# Sheet1.net
KiCad netlist of a schematic drawn in Altium Designer
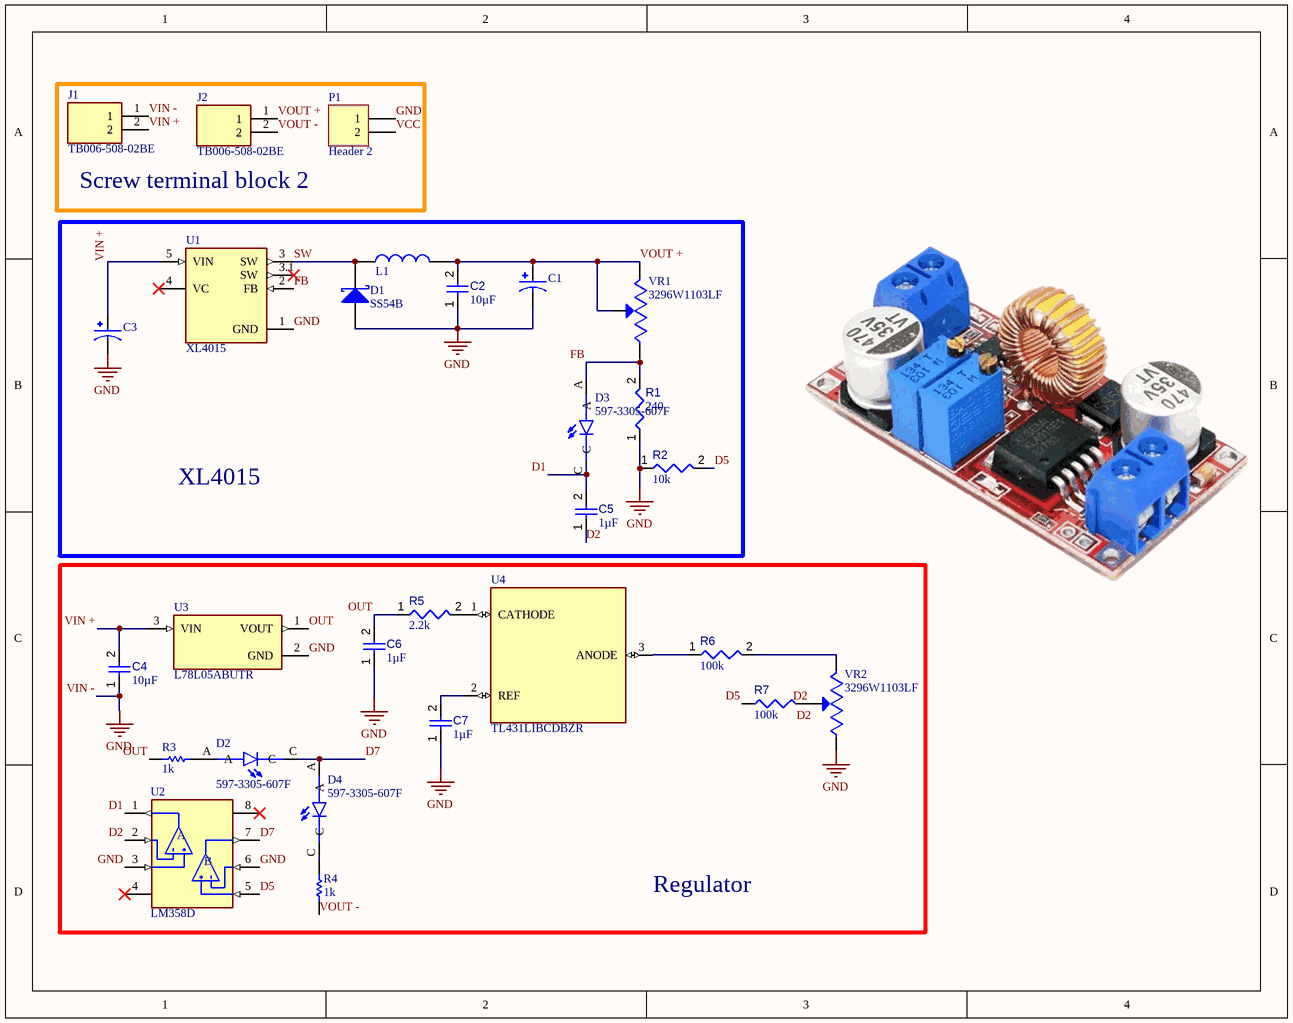
[diagram p0: Sheet1.SchDoc]

(export (version "E")
  (design (tool "Eeschema 10.0.6"))
  (components
    (comp (ref "C1")
      (value "EEEFN1V471UP")
      (footprint "CAP_EEEFN1V471UP")
      (description "CAP ALUM 470UF 20% 35V SMD")
      (fields (field (name "MF") "Panasonic Electronic Components") (field (name "MP") "EEE-FN1V471UP"))
      (libsource (lib "CAP ALUM 470UF") (part "EEEFN1V471UP"))
    )
    (comp (ref "C2")
      (value "10µF")
      (footprint "CAPC0603(1608)100_L")
      (description "Chip Capacitor, 10µF +/-20%, 10V, 0603, Thickness 1 mm")
      (fields (field (name "TOLERANCE") "10%") (field (name "Comment") "Capacitor 10µF +/-20% 10V 0603"))
      (libsource (lib "Med khalil khlifi") (part "CAP-NP-2"))
    )
    (comp (ref "C3")
      (value "EEEFN1V471UP")
      (footprint "CAP_EEEFN1V471UP")
      (description "CAP ALUM 470UF 20% 35V SMD")
      (fields (field (name "MF") "Panasonic Electronic Components") (field (name "MP") "EEE-FN1V471UP"))
      (libsource (lib "CAP ALUM 470UF") (part "EEEFN1V471UP"))
    )
    (comp (ref "C4")
      (value "10µF")
      (footprint "CAPC0603(1608)100_L")
      (description "Chip Capacitor, 10µF +/-20%, 10V, 0603, Thickness 1 mm")
      (fields (field (name "TOLERANCE") "10%") (field (name "Comment") "Capacitor 10µF +/-20% 10V 0603"))
      (libsource (lib "Med khalil khlifi") (part "CAP-NP-2"))
    )
    (comp (ref "C5")
      (value "1µF")
      (footprint "CAPC2013X145X50ML20T25")
      (description "Chip Capacitor, 1 uF, +/-10%, 25 V, 0805 (2012 Metric)")
      (fields (field (name "TOLERANCE") "10%") (field (name "Comment") "Capacitor 1 uF +/- 10% 25 V 0805"))
      (libsource (lib "Med khalil khlifi") (part "CAP-NP-2"))
    )
    (comp (ref "C6")
      (value "1µF")
      (footprint "CAPC2013X145X50ML20T25")
      (description "Chip Capacitor, 1 uF, +/-10%, 25 V, 0805 (2012 Metric)")
      (fields (field (name "TOLERANCE") "10%") (field (name "Comment") "Capacitor 1 uF +/- 10% 25 V 0805"))
      (libsource (lib "Med khalil khlifi") (part "CAP-NP-2"))
    )
    (comp (ref "C7")
      (value "1µF")
      (footprint "CAPC2013X145X50ML20T25")
      (description "Chip Capacitor, 1 uF, +/-10%, 25 V, 0805 (2012 Metric)")
      (fields (field (name "TOLERANCE") "10%") (field (name "Comment") "Capacitor 1 uF +/- 10% 25 V 0805"))
      (libsource (lib "Med khalil khlifi") (part "CAP-NP-2"))
    )
    (comp (ref "D1")
      (value "SS54B")
      (footprint "JCET-SMB-2_M")
      (description "Schottky Barrier Rectifier, 40 V, 5 A, -55 to 150 degC, 2-Pin SMD")
      (fields (field (name "MANUFACTURER") "JCET"))
      (libsource (lib "Med khalil khlifi") (part "DSKY-AK-2"))
    )
    (comp (ref "D2")
      (value "597-3305-607F")
      (footprint "LEDC2012X70N")
      (description "LED Uni-Color Green 4-Pin Chip 0805 T/R")
      (libsource (lib "Led") (part "597-3305-607F"))
    )
    (comp (ref "D3")
      (value "597-3305-607F")
      (footprint "LEDC2012X70N")
      (description "LED Uni-Color Green 4-Pin Chip 0805 T/R")
      (libsource (lib "Led") (part "597-3305-607F"))
    )
    (comp (ref "D4")
      (value "597-3305-607F")
      (footprint "LEDC2012X70N")
      (description "LED Uni-Color Green 4-Pin Chip 0805 T/R")
      (libsource (lib "Led") (part "597-3305-607F"))
    )
    (comp (ref "J1")
      (value "TB006-508-02BE")
      (footprint "CUI_TB006-508-02BE")
      (description "2~24 Poles, Screw Type, Horizontal, 5.08 Pitch, 26~14 (AWG), Terminal Block Connector")
      (fields (field (name "MF") "Same Sky"))
      (libsource (lib "screw terminal block 2") (part "TB006-508-02BE"))
    )
    (comp (ref "J2")
      (value "TB006-508-02BE")
      (footprint "CUI_TB006-508-02BE")
      (description "2~24 Poles, Screw Type, Horizontal, 5.08 Pitch, 26~14 (AWG), Terminal Block Connector")
      (fields (field (name "MF") "Same Sky"))
      (libsource (lib "screw terminal block 2") (part "TB006-508-02BE"))
    )
    (comp (ref "L1")
      (value "15µH")
      (footprint "7447035")
      (description "WE-FI THT Leaded Toroidal Line Choke, 15µH, 4.5A, 0.025Ω")
      (fields
        (field (name "MANUFACTURER PART NUMBER") "7447035")
        (field (name "MANUFACTURER") "Wurth Elektronik")
      )
      (libsource (lib "Toroidal Inductor") (part "7447035"))
    )
    (comp (ref "P1")
      (value "Header 2")
      (footprint "HDR1X2")
      (description "Header, 2-Pin")
      (fields (field (name "PUBLISHER") "Altium Limited"))
      (libsource (lib "Med khalil khlifi") (part "Header 2H"))
    )
    (comp (ref "R1")
      (value "240")
      (footprint "RESC0402(1005)_L")
      (description "Chip Resistor, 240 Ohms, +/-5 %, 63 mW, -55 to 155 degC, 0402")
      (fields (field (name "POWER") "63mW") (field (name "TOLERANCE") "5%"))
      (libsource (lib "") (part "RES-2_1"))
    )
    (comp (ref "R2")
      (value "10k")
      (footprint "RESC0402(1005)_L")
      (description "Chip Resistor, 10 kOhms, +/-1 %, 63 mW, -55 to 125 degC, 0402")
      (fields (field (name "POWER") "63mW") (field (name "TOLERANCE") "1%"))
      (libsource (lib "") (part "RES-2_1"))
    )
    (comp (ref "R3")
      (value "1k")
      (footprint "RESC1005X40X25ML05T05")
      (description "Chip Resistor, 1 KOhm, +/- 1%, 0.1 W, -55 to 155 degC, 0402 (1005 Metric)")
      (fields (field (name "POWER") "100mW") (field (name "TOLERANCE") "1%"))
      (libsource (lib "Med khalil khlifi") (part "RES-2"))
    )
    (comp (ref "R4")
      (value "1k")
      (footprint "RESC1005X40X25ML05T05")
      (description "Chip Resistor, 1 KOhm, +/- 1%, 0.1 W, -55 to 155 degC, 0402 (1005 Metric)")
      (fields (field (name "POWER") "100mW") (field (name "TOLERANCE") "1%"))
      (libsource (lib "Med khalil khlifi") (part "RES-2"))
    )
    (comp (ref "R5")
      (value "2.2k")
      (footprint "RESC0402(1005)_L")
      (description "Chip Resistor, 2,2 kOhms, +/-5 %, 63 mW, -55 to 155 degC, 0402")
      (fields (field (name "POWER") "63mW") (field (name "TOLERANCE") "5%"))
      (libsource (lib "") (part "RES-2_1"))
    )
    (comp (ref "R6")
      (value "100k")
      (footprint "RESC1005X40X25ML05T05")
      (description "Chip Resistor, 100 KOhm, +/- 1%, 0.063 W, -55 to 155 degC, 0402 (1005 Metric)")
      (fields (field (name "TOLERANCE") "1%") (field (name "POWER") "63mW"))
      (libsource (lib "") (part "RES-2_1"))
    )
    (comp (ref "R7")
      (value "100k")
      (footprint "RESC1005X40X25ML05T05")
      (description "Chip Resistor, 100 KOhm, +/- 1%, 0.063 W, -55 to 155 degC, 0402 (1005 Metric)")
      (fields (field (name "TOLERANCE") "1%") (field (name "POWER") "63mW"))
      (libsource (lib "") (part "RES-2_2"))
    )
    (comp (ref "U1")
      (value "XL4015")
      (footprint "CONV_XL4015")
      (description "5A 180KHz 36V Buck DC to DC Converter")
      (fields (field (name "MF") "XLSEMI"))
      (libsource (lib "XL4015") (part "XL4015"))
    )
    (comp (ref "U2")
      (value "LM358D")
      (footprint "SOIC127P599X175-8N")
      (description "Op Amp Dual Low Power Amplifier Â±15V/30V 8-Pin SO N Tube")
      (fields (field (name "MF") "STMicroelectronics"))
      (libsource (lib "LM358D") (part "LM358D"))
    )
    (comp (ref "U3")
      (value "L78L05ABUTR")
      (footprint "VREG_L78L05ABUTR")
      (description "Linear Voltage Regulator IC Positive Fixed 1 Output 100mA SOT-89-3")
      (fields (field (name "MF") "STMicroelectronics"))
      (libsource (lib "L78L05ABUTR") (part "L78L05ABUTR"))
    )
    (comp (ref "U4")
      (value "TL431LIBCDBZR")
      (footprint "SOT23")
      (description "Adjustable precision shunt regulator with optimized reference current (pin layout: KRA)")
      (fields (field (name "MF") "Texas Instruments"))
      (libsource (lib "TL431LIBCDBZR") (part "TL431LIBCDBZR"))
    )
    (comp (ref "VR1")
      (value "3296W1103LF")
      (footprint "TRIM_3296W1103LF")
      (description "Trimmer, Potentiometer 10kohm 25turn Thd")
      (fields (field (name "MF") "Bourns"))
      (libsource (lib "Potentiometer 1") (part "3296W1103LF"))
    )
    (comp (ref "VR2")
      (value "3296W1103LF")
      (footprint "TRIM_3296W1103LF")
      (description "Trimmer, Potentiometer 10kohm 25turn Thd")
      (fields (field (name "MF") "Bourns"))
      (libsource (lib "Potentiometer 1") (part "3296W1103LF"))
    )
  )
  (nets
    (net (code "1") (name "/D1") (class "Default")
      (node (ref "C5") (pin "2") (pinfunction "2_2") (pintype "passive"))
      (node (ref "D3") (pin "C") (pinfunction "C_C") (pintype "passive"))
      (node (ref "U2") (pin "1") (pinfunction "OUT1_1") (pintype "output"))
    )
    (net (code "2") (name "/D2") (class "Default")
      (node (ref "C5") (pin "1") (pinfunction "1_1") (pintype "passive"))
      (node (ref "R7") (pin "2") (pinfunction "2_2") (pintype "passive"))
      (node (ref "U2") (pin "2") (pinfunction "IN1-_2") (pintype "input"))
      (node (ref "VR2") (pin "2") (pinfunction "WIPER_2") (pintype "passive"))
    )
    (net (code "3") (name "/D5") (class "Default")
      (node (ref "R2") (pin "2") (pinfunction "2_2") (pintype "passive"))
      (node (ref "R7") (pin "1") (pinfunction "1_1") (pintype "passive"))
      (node (ref "U2") (pin "5") (pinfunction "IN2+_5") (pintype "input"))
    )
    (net (code "4") (name "/D7") (class "Default")
      (node (ref "D2") (pin "C") (pinfunction "C_C") (pintype "passive"))
      (node (ref "D4") (pin "A") (pinfunction "A_A") (pintype "passive"))
      (node (ref "U2") (pin "7") (pinfunction "OUT2_7") (pintype "output"))
    )
    (net (code "5") (name "/FB") (class "Default")
      (node (ref "D3") (pin "A") (pinfunction "A_A") (pintype "passive"))
      (node (ref "R1") (pin "2") (pinfunction "2_2") (pintype "passive"))
      (node (ref "U1") (pin "2") (pinfunction "FB_2") (pintype "input"))
      (node (ref "VR1") (pin "1") (pinfunction "CCW_1") (pintype "passive"))
    )
    (net (code "6") (name "/OUT") (class "Default")
      (node (ref "C6") (pin "2") (pinfunction "2_2") (pintype "passive"))
      (node (ref "R3") (pin "1") (pinfunction "1_1") (pintype "passive"))
      (node (ref "R5") (pin "1") (pinfunction "1_1") (pintype "passive"))
      (node (ref "U3") (pin "1") (pinfunction "VOUT_1") (pintype "output"))
    )
    (net (code "7") (name "/SW") (class "Default")
      (node (ref "D1") (pin "2") (pinfunction "K_2") (pintype "passive"))
      (node (ref "L1") (pin "1") (pinfunction "1_1") (pintype "passive"))
      (node (ref "U1") (pin "3") (pinfunction "SW_3") (pintype "output"))
    )
    (net (code "8") (name "/VCC") (class "Default")
      (node (ref "P1") (pin "2") (pinfunction "2_2") (pintype "passive"))
    )
    (net (code "9") (name "/VIN +") (class "Default")
      (node (ref "C3") (pin "1") (pinfunction "1_1") (pintype "passive"))
      (node (ref "C4") (pin "2") (pinfunction "2_2") (pintype "passive"))
      (node (ref "J1") (pin "2") (pinfunction "2_2") (pintype "passive"))
      (node (ref "U1") (pin "5") (pinfunction "VIN_5") (pintype "input"))
      (node (ref "U3") (pin "3") (pinfunction "VIN_3") (pintype "input"))
    )
    (net (code "10") (name "/VOUT +") (class "Default")
      (node (ref "C1") (pin "1") (pinfunction "1_1") (pintype "passive"))
      (node (ref "C2") (pin "2") (pinfunction "2_2") (pintype "passive"))
      (node (ref "J2") (pin "1") (pinfunction "1_1") (pintype "passive"))
      (node (ref "L1") (pin "2") (pinfunction "2_2") (pintype "passive"))
      (node (ref "VR1") (pin "2") (pinfunction "WIPER_2") (pintype "passive"))
      (node (ref "VR1") (pin "3") (pinfunction "CW_3") (pintype "passive"))
    )
    (net (code "11") (name "/VOUT -") (class "Default")
      (node (ref "J2") (pin "2") (pinfunction "2_2") (pintype "passive"))
      (node (ref "R4") (pin "1") (pinfunction "1_1") (pintype "passive"))
    )
    (net (code "12") (name "GND") (class "Default")
      (node (ref "C1") (pin "2") (pinfunction "2_2") (pintype "passive"))
      (node (ref "C2") (pin "1") (pinfunction "1_1") (pintype "passive"))
      (node (ref "C3") (pin "2") (pinfunction "2_2") (pintype "passive"))
      (node (ref "C4") (pin "1") (pinfunction "1_1") (pintype "passive"))
      (node (ref "C6") (pin "1") (pinfunction "1_1") (pintype "passive"))
      (node (ref "C7") (pin "1") (pinfunction "1_1") (pintype "passive"))
      (node (ref "D1") (pin "1") (pinfunction "A_1") (pintype "passive"))
      (node (ref "J1") (pin "1") (pinfunction "1_1") (pintype "passive"))
      (node (ref "P1") (pin "1") (pinfunction "1_1") (pintype "passive"))
      (node (ref "R1") (pin "1") (pinfunction "1_1") (pintype "passive"))
      (node (ref "R2") (pin "1") (pinfunction "1_1") (pintype "passive"))
      (node (ref "U1") (pin "1") (pinfunction "GND_1") (pintype "power_in"))
      (node (ref "U2") (pin "3") (pinfunction "IN1+_3") (pintype "input"))
      (node (ref "U2") (pin "6") (pinfunction "IN2-_6") (pintype "input"))
      (node (ref "U3") (pin "2") (pinfunction "GND_2") (pintype "power_in"))
      (node (ref "VR2") (pin "1") (pinfunction "CCW_1") (pintype "passive"))
    )
    (net (code "13") (name "Net-(D2-PadA)") (class "Default")
      (node (ref "D2") (pin "A") (pinfunction "A_A") (pintype "passive"))
      (node (ref "R3") (pin "2") (pinfunction "2_2") (pintype "passive"))
    )
    (net (code "14") (name "Net-(D4-PadC)") (class "Default")
      (node (ref "D4") (pin "C") (pinfunction "C_C") (pintype "passive"))
      (node (ref "R4") (pin "2") (pinfunction "2_2") (pintype "passive"))
    )
    (net (code "15") (name "Net-(U4-ANODE)") (class "Default")
      (node (ref "R6") (pin "1") (pinfunction "1_1") (pintype "passive"))
      (node (ref "U4") (pin "3") (pinfunction "ANODE_3") (pintype "bidirectional"))
    )
    (net (code "16") (name "Net-(U4-CATHODE)") (class "Default")
      (node (ref "R5") (pin "2") (pinfunction "2_2") (pintype "passive"))
      (node (ref "U4") (pin "1") (pinfunction "CATHODE_1") (pintype "bidirectional"))
    )
    (net (code "17") (name "Net-(U4-REF)") (class "Default")
      (node (ref "C7") (pin "2") (pinfunction "2_2") (pintype "passive"))
      (node (ref "U4") (pin "2") (pinfunction "REF_2") (pintype "bidirectional"))
    )
    (net (code "18") (name "Net-(VR2-CW)") (class "Default")
      (node (ref "R6") (pin "2") (pinfunction "2_2") (pintype "passive"))
      (node (ref "VR2") (pin "3") (pinfunction "CW_3") (pintype "passive"))
    )
    (net (code "19") (name "unconnected-(U1-SW-Pad3.1)") (class "Default")
      (node (ref "U1") (pin "3.1") (pinfunction "SW_3.1") (pintype "output+no_connect"))
    )
    (net (code "20") (name "unconnected-(U1-VC-Pad4)") (class "Default")
      (node (ref "U1") (pin "4") (pinfunction "VC_4") (pintype "passive+no_connect"))
    )
    (net (code "21") (name "unconnected-(U2-V+-Pad8)") (class "Default")
      (node (ref "U2") (pin "8") (pinfunction "V+_8") (pintype "power_in+no_connect"))
    )
    (net (code "22") (name "unconnected-(U2-V--Pad4)") (class "Default")
      (node (ref "U2") (pin "4") (pinfunction "V-_4") (pintype "power_in+no_connect"))
    )
  )
)
